# Sensors.net
KiCad netlist of a schematic drawn in Altium Designer
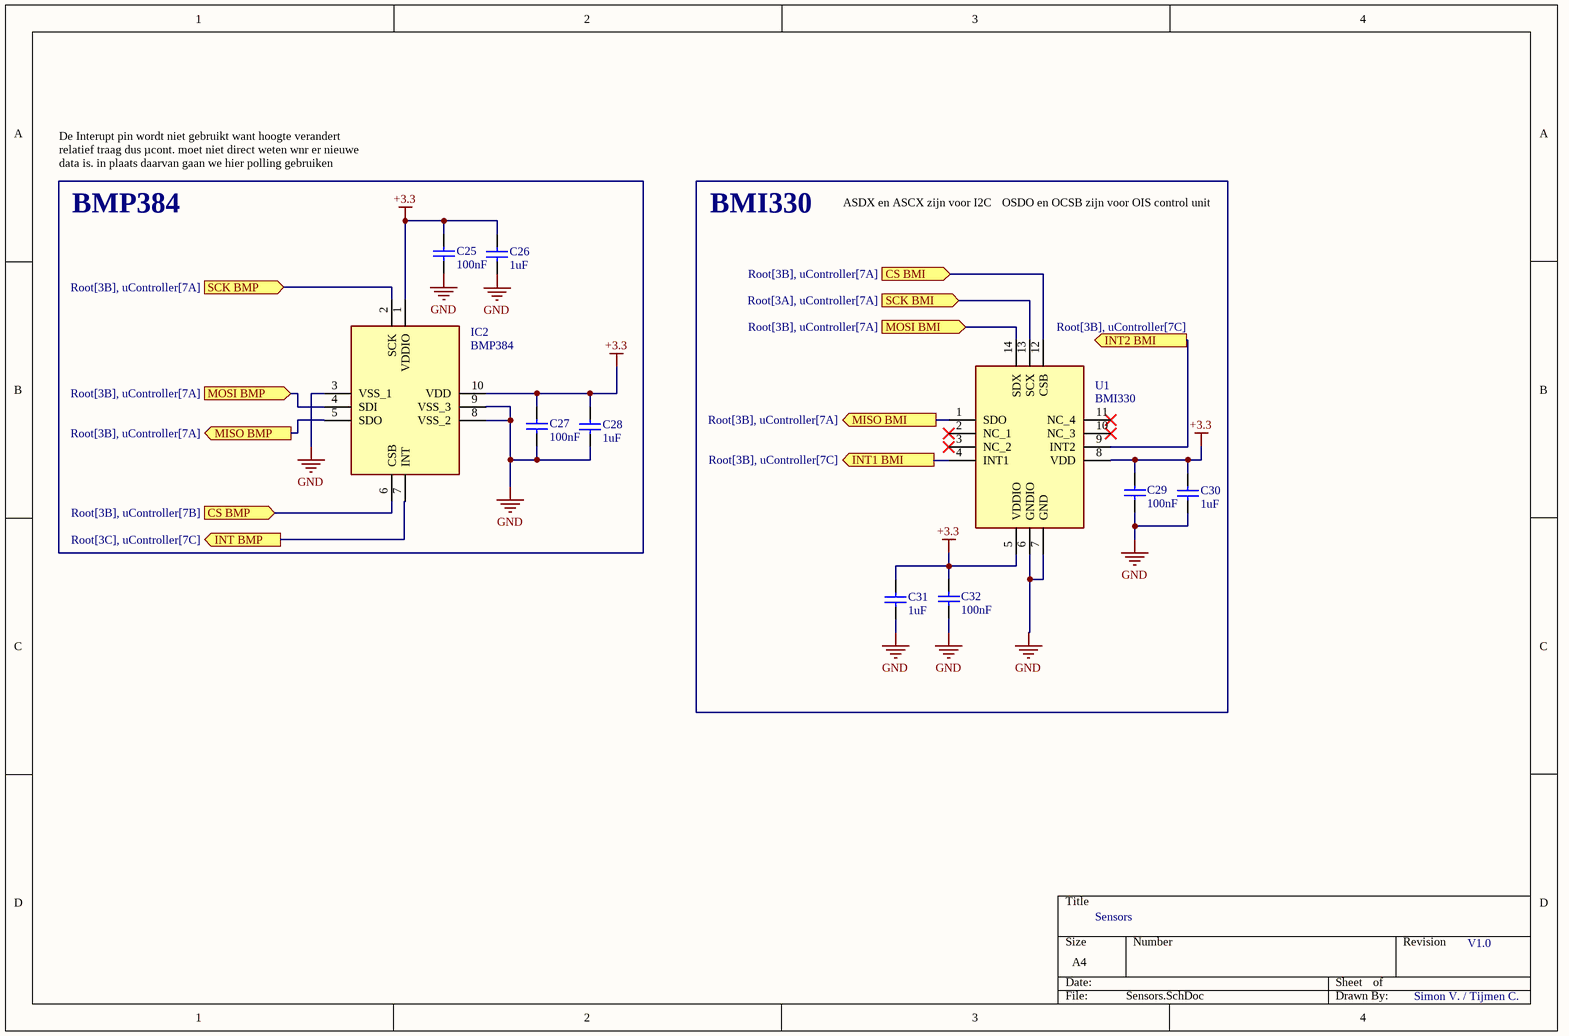
[diagram p0: Sensors.SchDoc]

(export (version "E")
  (design (tool "Eeschema 10.0.6"))
  (components
    (comp (ref "C25")
      (value "100nF")
      (footprint "CAPC1608X92X38ML15T08")
      (fields (field (name "PART NUMBER") "VJ0603Y104MXXAC") (field (name "MANUFACTURER") "Vitramon"))
      (libsource (lib "Altium Content Vault") (part "CAP"))
    )
    (comp (ref "C26")
      (value "1uF")
      (footprint "CAPC1608X90X35NL15T15")
      (fields
        (field (name "PART NUMBER") "0603YD105MAT2A")
        (field (name "MANUFACTURER") "AVX Interconnect / Elco")
      )
      (libsource (lib "Altium Content Vault") (part "CAP"))
    )
    (comp (ref "C27")
      (value "100nF")
      (footprint "CAPC1608X92X38ML15T08")
      (fields (field (name "PART NUMBER") "VJ0603Y104MXXAC") (field (name "MANUFACTURER") "Vitramon"))
      (libsource (lib "Altium Content Vault") (part "CAP"))
    )
    (comp (ref "C28")
      (value "1uF")
      (footprint "CAPC1608X90X35NL15T15")
      (fields
        (field (name "PART NUMBER") "0603YD105MAT2A")
        (field (name "MANUFACTURER") "AVX Interconnect / Elco")
      )
      (libsource (lib "Altium Content Vault") (part "CAP"))
    )
    (comp (ref "C29")
      (value "100nF")
      (footprint "CAPC1608X92X38ML15T08")
      (fields (field (name "PART NUMBER") "VJ0603Y104MXXAC") (field (name "MANUFACTURER") "Vitramon"))
      (libsource (lib "Altium Content Vault") (part "CAP"))
    )
    (comp (ref "C30")
      (value "1uF")
      (footprint "CAPC1608X90X35NL15T15")
      (fields
        (field (name "PART NUMBER") "0603YD105MAT2A")
        (field (name "MANUFACTURER") "AVX Interconnect / Elco")
      )
      (libsource (lib "Altium Content Vault") (part "CAP"))
    )
    (comp (ref "C31")
      (value "1uF")
      (footprint "CAPC1608X90X35NL15T15")
      (fields
        (field (name "PART NUMBER") "0603YD105MAT2A")
        (field (name "MANUFACTURER") "AVX Interconnect / Elco")
      )
      (libsource (lib "Altium Content Vault") (part "CAP"))
    )
    (comp (ref "C32")
      (value "100nF")
      (footprint "CAPC1608X92X38ML15T08")
      (fields (field (name "PART NUMBER") "VJ0603Y104MXXAC") (field (name "MANUFACTURER") "Vitramon"))
      (libsource (lib "Altium Content Vault") (part "CAP"))
    )
    (comp (ref "IC2")
      (value "BMP384")
      (footprint "SamacSys:BMP384")
      (description "Integrated Circuit")
      (fields (field (name "MOUSER PART NUMBER") "262-BMP384"))
      (libsource (lib "*") (part "BMP384"))
    )
    (comp (ref "U1")
      (value "BMI330")
      (footprint "SamacSys:BMI330")
      (description "Undefined or Miscellaneous")
      (libsource (lib "*") (part "BMI330"))
    )
  )
  (nets
    (net (code "1") (name "+3.3") (class "Default")
      (node (ref "C25") (pin "2") (pinfunction "2_2") (pintype "passive"))
      (node (ref "C26") (pin "2") (pinfunction "2_2") (pintype "passive"))
      (node (ref "C27") (pin "2") (pinfunction "2_2") (pintype "passive"))
      (node (ref "C28") (pin "2") (pinfunction "2_2") (pintype "passive"))
      (node (ref "C29") (pin "2") (pinfunction "2_2") (pintype "passive"))
      (node (ref "C30") (pin "2") (pinfunction "2_2") (pintype "passive"))
      (node (ref "C31") (pin "2") (pinfunction "2_2") (pintype "passive"))
      (node (ref "C32") (pin "2") (pinfunction "2_2") (pintype "passive"))
      (node (ref "IC2") (pin "1") (pinfunction "VDDIO_1") (pintype "passive"))
      (node (ref "IC2") (pin "10") (pinfunction "VDD_10") (pintype "passive"))
      (node (ref "U1") (pin "5") (pinfunction "VDDIO_5") (pintype "passive"))
      (node (ref "U1") (pin "8") (pinfunction "VDD_8") (pintype "passive"))
    )
    (net (code "2") (name "/CS BMI") (class "Default")
      (node (ref "U1") (pin "12") (pinfunction "CSB_12") (pintype "passive"))
    )
    (net (code "3") (name "/CS BMP") (class "Default")
      (node (ref "IC2") (pin "6") (pinfunction "CSB_6") (pintype "passive"))
    )
    (net (code "4") (name "/INT BMP") (class "Default")
      (node (ref "IC2") (pin "7") (pinfunction "INT_7") (pintype "passive"))
    )
    (net (code "5") (name "/INT1 BMI") (class "Default")
      (node (ref "U1") (pin "4") (pinfunction "INT1_4") (pintype "passive"))
    )
    (net (code "6") (name "/INT2 BMI") (class "Default")
      (node (ref "U1") (pin "9") (pinfunction "INT2_9") (pintype "passive"))
    )
    (net (code "7") (name "/MISO BMI") (class "Default")
      (node (ref "U1") (pin "1") (pinfunction "SDO_1") (pintype "passive"))
    )
    (net (code "8") (name "/MISO BMP") (class "Default")
      (node (ref "IC2") (pin "5") (pinfunction "SDO_5") (pintype "passive"))
    )
    (net (code "9") (name "/MOSI BMI") (class "Default")
      (node (ref "U1") (pin "14") (pinfunction "SDX_14") (pintype "passive"))
    )
    (net (code "10") (name "/MOSI BMP") (class "Default")
      (node (ref "IC2") (pin "4") (pinfunction "SDI_4") (pintype "passive"))
    )
    (net (code "11") (name "/SCK BMI") (class "Default")
      (node (ref "U1") (pin "13") (pinfunction "SCX_13") (pintype "passive"))
    )
    (net (code "12") (name "/SCK BMP") (class "Default")
      (node (ref "IC2") (pin "2") (pinfunction "SCK_2") (pintype "passive"))
    )
    (net (code "13") (name "GND") (class "Default")
      (node (ref "C25") (pin "1") (pinfunction "1_1") (pintype "passive"))
      (node (ref "C26") (pin "1") (pinfunction "1_1") (pintype "passive"))
      (node (ref "C27") (pin "1") (pinfunction "1_1") (pintype "passive"))
      (node (ref "C28") (pin "1") (pinfunction "1_1") (pintype "passive"))
      (node (ref "C29") (pin "1") (pinfunction "1_1") (pintype "passive"))
      (node (ref "C30") (pin "1") (pinfunction "1_1") (pintype "passive"))
      (node (ref "C31") (pin "1") (pinfunction "1_1") (pintype "passive"))
      (node (ref "C32") (pin "1") (pinfunction "1_1") (pintype "passive"))
      (node (ref "IC2") (pin "3") (pinfunction "VSS_1_3") (pintype "passive"))
      (node (ref "IC2") (pin "8") (pinfunction "VSS_2_8") (pintype "passive"))
      (node (ref "IC2") (pin "9") (pinfunction "VSS_3_9") (pintype "passive"))
      (node (ref "U1") (pin "6") (pinfunction "GNDIO_6") (pintype "passive"))
      (node (ref "U1") (pin "7") (pinfunction "GND_7") (pintype "passive"))
    )
    (net (code "14") (name "unconnected-(U1-NC_1-Pad2)") (class "Default")
      (node (ref "U1") (pin "2") (pinfunction "NC_1_2") (pintype "passive+no_connect"))
    )
    (net (code "15") (name "unconnected-(U1-NC_2-Pad3)") (class "Default")
      (node (ref "U1") (pin "3") (pinfunction "NC_2_3") (pintype "passive+no_connect"))
    )
    (net (code "16") (name "unconnected-(U1-NC_3-Pad10)") (class "Default")
      (node (ref "U1") (pin "10") (pinfunction "NC_3_10") (pintype "passive+no_connect"))
    )
    (net (code "17") (name "unconnected-(U1-NC_4-Pad11)") (class "Default")
      (node (ref "U1") (pin "11") (pinfunction "NC_4_11") (pintype "passive+no_connect"))
    )
  )
)
